# ProPrj_VacUBear_2026-03-05.net
KiCad netlist of a schematic drawn in EasyEDA Pro
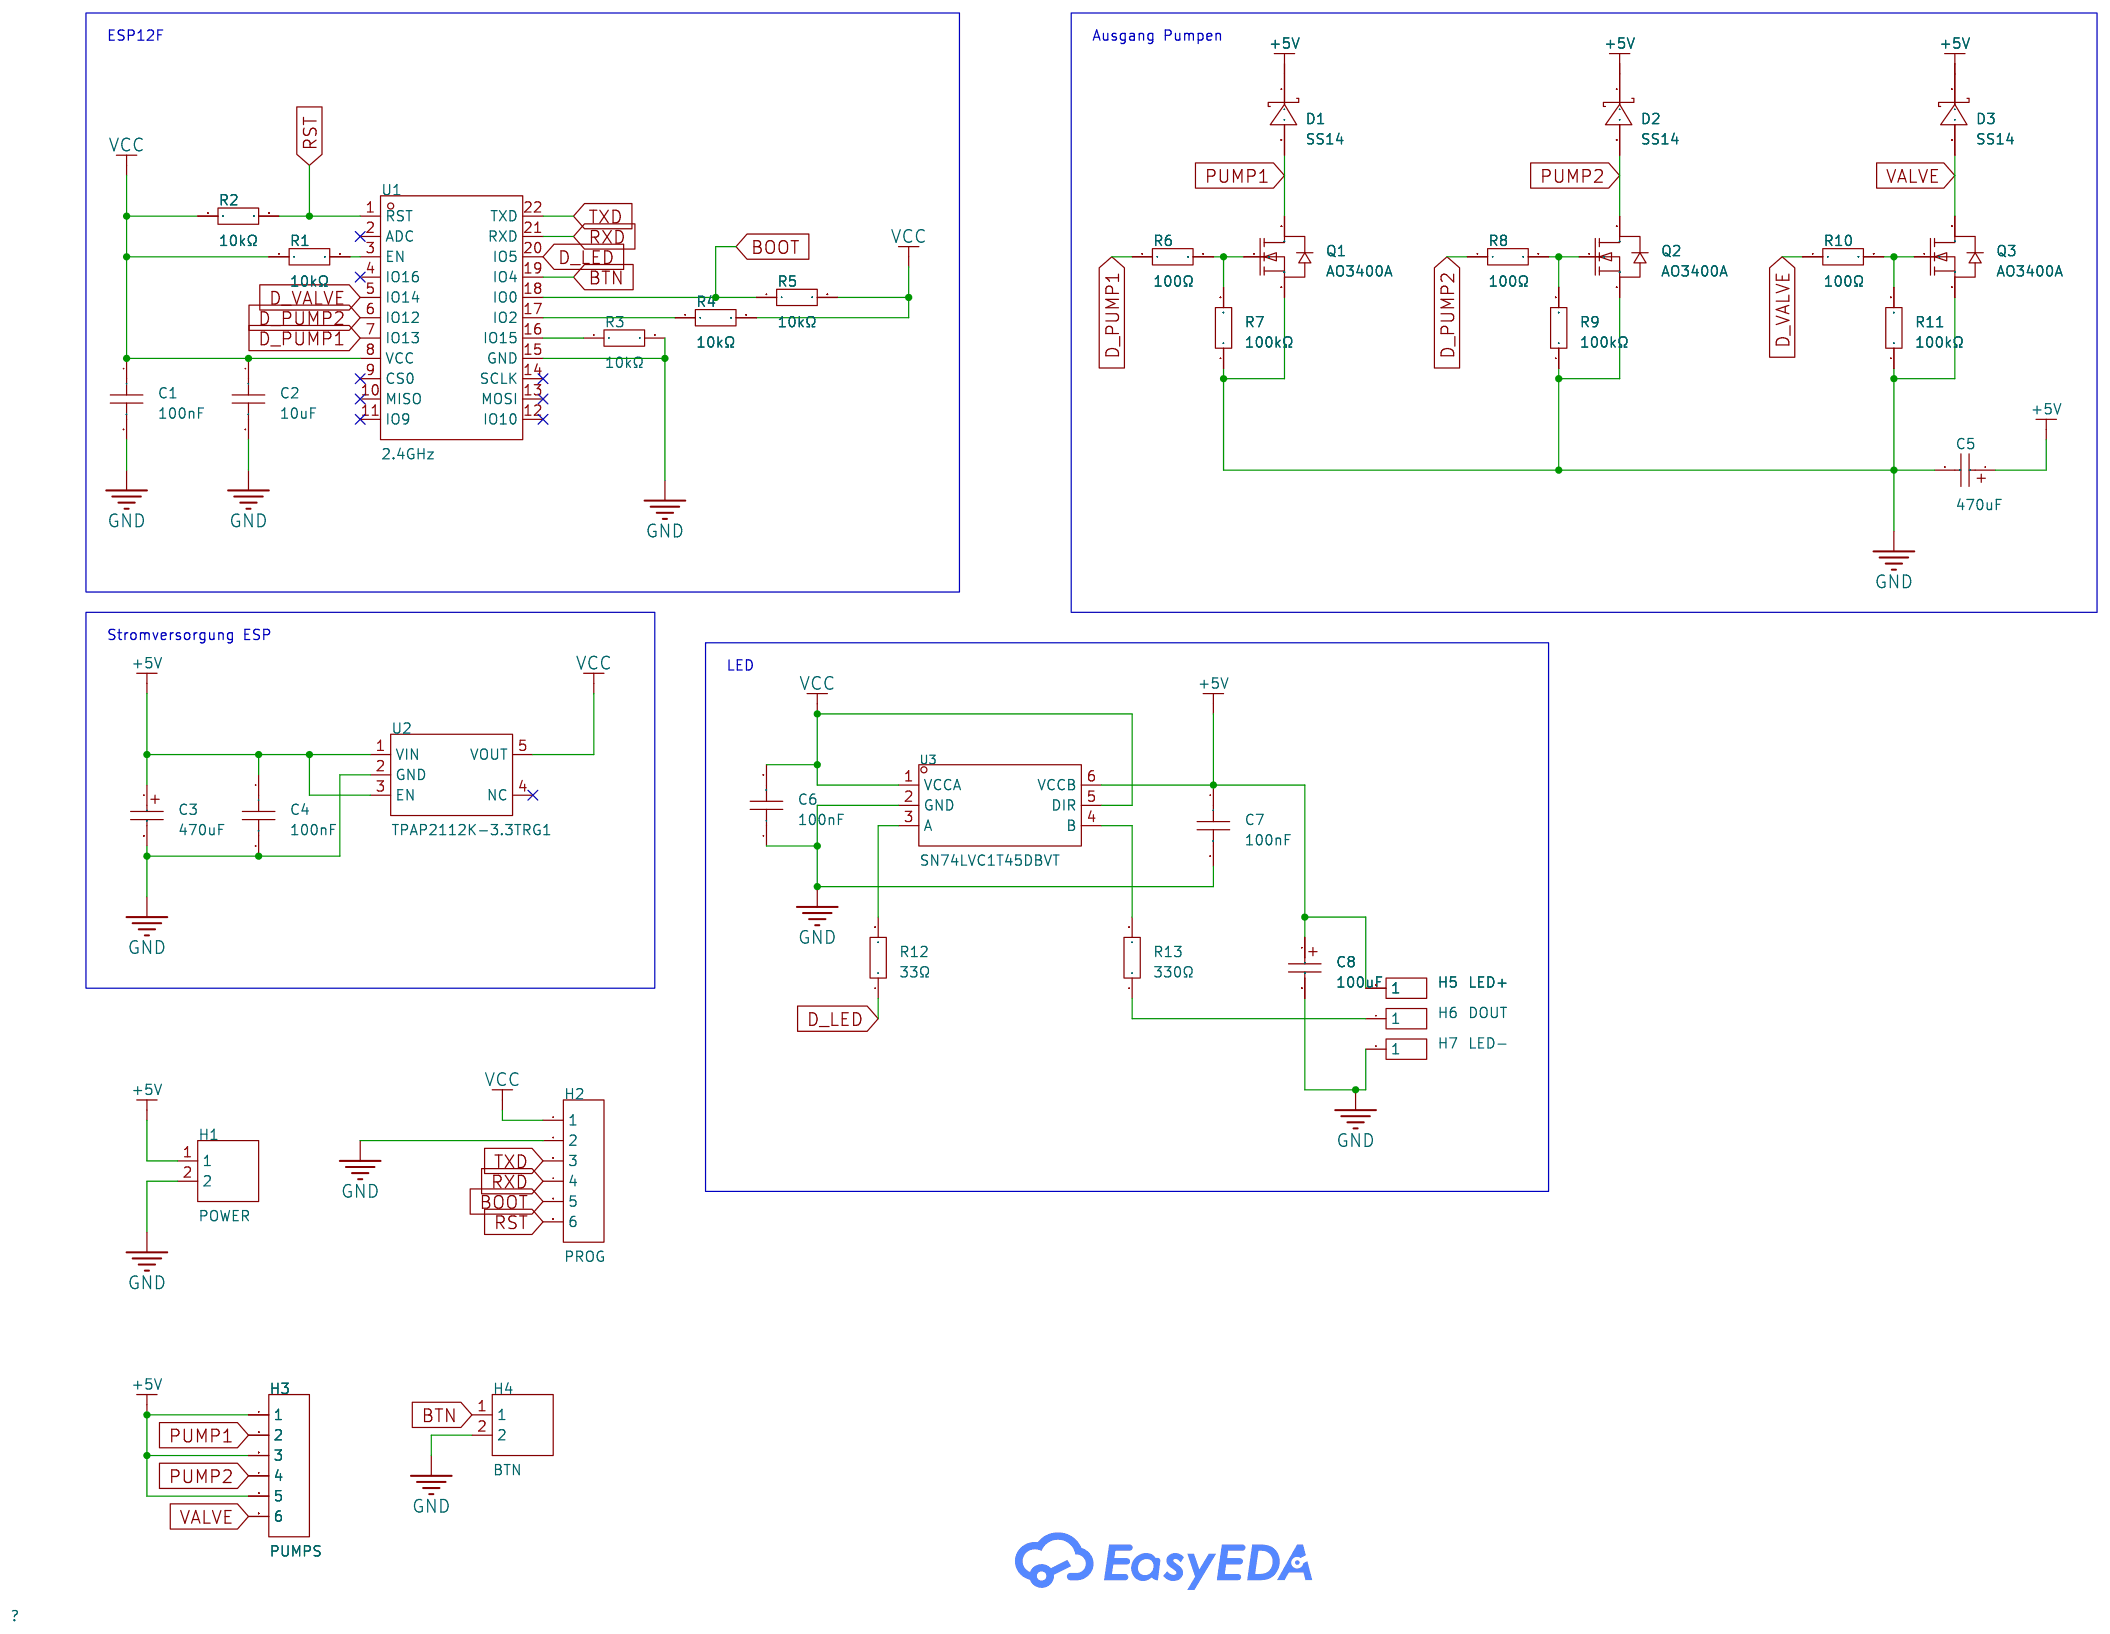
[diagram p0: schematic sheet]

(export (version "E")
  (design (tool "Eeschema 10.0.6"))
  (components
    (comp (ref "C1")
      (value "100nF")
      (footprint "easyedapro:C0402")
      (description "Capacitance:100nF Tolerance:±10% Tolerance:±10% Voltage Rating:50V Temperature Coefficient:X7R")
      (fields
        (field (name "Manufacturer Part") "CL05B104KB54PNC")
        (field (name "Manufacturer") "SAMSUNG(三星)")
      )
      (libsource (lib "easyedapro") (part "CAP"))
    )
    (comp (ref "C2")
      (value "10uF")
      (footprint "easyedapro:C0402")
      (description "Capacitance:10uF Tolerance:±20% Tolerance:±20% Voltage Rating:6.3V Temperature Coefficient:X5R")
      (fields
        (field (name "Manufacturer Part") "CL10A106MQ8NNNC")
        (field (name "Manufacturer") "SAMSUNG(三星)")
      )
      (libsource (lib "easyedapro") (part "CAP"))
    )
    (comp (ref "C3")
      (value "470uF")
      (footprint "easyedapro:CAP-SMD_BD3.0-L3.3-W3.3-RD")
      (fields (field (name "Manufacturer Part") "RVT1C471M0607") (field (name "Manufacturer") "ROQANG(容强)"))
      (libsource (lib "easyedapro") (part "C_Ele_SMD"))
    )
    (comp (ref "C4")
      (value "100nF")
      (footprint "easyedapro:C0402")
      (description "Capacitance:100nF Tolerance:±10% Tolerance:±10% Voltage Rating:50V Temperature Coefficient:X7R")
      (fields
        (field (name "Manufacturer Part") "CL05B104KB54PNC")
        (field (name "Manufacturer") "SAMSUNG(三星)")
      )
      (libsource (lib "easyedapro") (part "CAP"))
    )
    (comp (ref "C5")
      (value "470uF")
      (footprint "easyedapro:CAP-SMD_BD3.0-L3.3-W3.3-RD")
      (fields (field (name "Manufacturer Part") "RVT1C471M0607") (field (name "Manufacturer") "ROQANG(容强)"))
      (libsource (lib "easyedapro") (part "C_Ele_SMD"))
    )
    (comp (ref "C6")
      (value "100nF")
      (footprint "easyedapro:C0402")
      (description "Capacitance:100nF Tolerance:±10% Tolerance:±10% Voltage Rating:50V Temperature Coefficient:X7R")
      (fields
        (field (name "Manufacturer Part") "CL05B104KB54PNC")
        (field (name "Manufacturer") "SAMSUNG(三星)")
      )
      (libsource (lib "easyedapro") (part "CAP"))
    )
    (comp (ref "C7")
      (value "100nF")
      (footprint "easyedapro:C0402")
      (description "Capacitance:100nF Tolerance:±10% Tolerance:±10% Voltage Rating:50V Temperature Coefficient:X7R")
      (fields
        (field (name "Manufacturer Part") "CL05B104KB54PNC")
        (field (name "Manufacturer") "SAMSUNG(三星)")
      )
      (libsource (lib "easyedapro") (part "CAP"))
    )
    (comp (ref "C8")
      (value "100uF")
      (footprint "easyedapro:CAP-SMD_BD3.0-L3.3-W3.3-RD")
      (fields
        (field (name "Manufacturer Part") "RVT100UF16V67RV0016")
        (field (name "Manufacturer") "KNSCHA(科尼盛)")
      )
      (libsource (lib "easyedapro") (part "C_Ele_SMD"))
    )
    (comp (ref "D1")
      (value "SS14")
      (footprint "easyedapro:SMA_L4.2-W2.6-LS5.0-RD_1")
      (fields (field (name "Manufacturer") "MDD(辰达半导体)"))
      (libsource (lib "easyedapro") (part "SS14"))
    )
    (comp (ref "D2")
      (value "SS14")
      (footprint "easyedapro:SMA_L4.2-W2.6-LS5.0-RD_1")
      (fields (field (name "Manufacturer") "MDD(辰达半导体)"))
      (libsource (lib "easyedapro") (part "SS14"))
    )
    (comp (ref "D3")
      (value "SS14")
      (footprint "easyedapro:SMA_L4.2-W2.6-LS5.0-RD_1")
      (fields (field (name "Manufacturer") "MDD(辰达半导体)"))
      (libsource (lib "easyedapro") (part "SS14"))
    )
    (comp (ref "H1")
      (value "POWER")
      (footprint "easyedapro:HDR-TH_2P-P2.54-V-M-1")
      (libsource (lib "easyedapro") (part "210S-1*2P L=11.6MMGold-plated black"))
    )
    (comp (ref "H2")
      (value "PROG")
      (footprint "easyedapro:HDR-TH_6P-P2.54-V-M-1")
      (libsource (lib "easyedapro") (part "Header-Male-2.54_1x6"))
    )
    (comp (ref "H3")
      (value "PUMPS")
      (footprint "easyedapro:HDR-TH_6P-P2.54-V-M-1")
      (libsource (lib "easyedapro") (part "Header-Male-2.54_1x6"))
    )
    (comp (ref "H4")
      (value "BTN")
      (footprint "easyedapro:HDR-TH_2P-P2.54-V-M-1")
      (libsource (lib "easyedapro") (part "210S-1*2P L=11.6MMGold-plated black"))
    )
    (comp (ref "H5")
      (value "LED+")
      (footprint "easyedapro:HDR-TH_1P-V-M_XKB_X4611WV-01I-C28D40")
      (libsource (lib "easyedapro") (part "HDR_1x1"))
    )
    (comp (ref "H6")
      (value "DOUT")
      (footprint "easyedapro:HDR-TH_1P-V-M_XKB_X4611WV-01I-C28D40")
      (libsource (lib "easyedapro") (part "HDR_1x1"))
    )
    (comp (ref "H7")
      (value "LED-")
      (footprint "easyedapro:HDR-TH_1P-V-M_XKB_X4611WV-01I-C28D40")
      (libsource (lib "easyedapro") (part "HDR_1x1"))
    )
    (comp (ref "Q1")
      (value "AO3400A")
      (footprint "easyedapro:SOT-23-3_L2.9-W1.3-P1.90-LS2.4-BR")
      (fields (field (name "Manufacturer") "HUASHUO(华朔)"))
      (libsource (lib "easyedapro") (part "AO3400A_C700953"))
    )
    (comp (ref "Q2")
      (value "AO3400A")
      (footprint "easyedapro:SOT-23-3_L2.9-W1.3-P1.90-LS2.4-BR")
      (fields (field (name "Manufacturer") "HUASHUO(华朔)"))
      (libsource (lib "easyedapro") (part "AO3400A_C700953"))
    )
    (comp (ref "Q3")
      (value "AO3400A")
      (footprint "easyedapro:SOT-23-3_L2.9-W1.3-P1.90-LS2.4-BR")
      (fields (field (name "Manufacturer") "HUASHUO(华朔)"))
      (libsource (lib "easyedapro") (part "AO3400A_C700953"))
    )
    (comp (ref "R1")
      (value "10kΩ")
      (footprint "easyedapro:R0402")
      (fields (field (name "Manufacturer Part") "RC0402JR-0710KL") (field (name "Manufacturer") "YAGEO(国巨)"))
      (libsource (lib "easyedapro") (part "Res"))
    )
    (comp (ref "R2")
      (value "10kΩ")
      (footprint "easyedapro:R0402")
      (fields (field (name "Manufacturer Part") "RC0402JR-0710KL") (field (name "Manufacturer") "YAGEO(国巨)"))
      (libsource (lib "easyedapro") (part "Res"))
    )
    (comp (ref "R3")
      (value "10kΩ")
      (footprint "easyedapro:R0402")
      (fields (field (name "Manufacturer Part") "RC0402JR-0710KL") (field (name "Manufacturer") "YAGEO(国巨)"))
      (libsource (lib "easyedapro") (part "Res"))
    )
    (comp (ref "R4")
      (value "10kΩ")
      (footprint "easyedapro:R0402")
      (fields (field (name "Manufacturer Part") "RC0402JR-0710KL") (field (name "Manufacturer") "YAGEO(国巨)"))
      (libsource (lib "easyedapro") (part "Res"))
    )
    (comp (ref "R5")
      (value "10kΩ")
      (footprint "easyedapro:R0402")
      (fields (field (name "Manufacturer Part") "RC0402JR-0710KL") (field (name "Manufacturer") "YAGEO(国巨)"))
      (libsource (lib "easyedapro") (part "Res"))
    )
    (comp (ref "R6")
      (value "100Ω")
      (footprint "easyedapro:R0402")
      (fields (field (name "Manufacturer Part") "FRC0402F1000TS") (field (name "Manufacturer") "FOJAN(富捷)"))
      (libsource (lib "easyedapro") (part "Res"))
    )
    (comp (ref "R7")
      (value "100kΩ")
      (footprint "easyedapro:R0402")
      (fields (field (name "Manufacturer Part") "RC0402FR-07100KL") (field (name "Manufacturer") "YAGEO(国巨)"))
      (libsource (lib "easyedapro") (part "Res"))
    )
    (comp (ref "R8")
      (value "100Ω")
      (footprint "easyedapro:R0402")
      (fields (field (name "Manufacturer Part") "FRC0402F1000TS") (field (name "Manufacturer") "FOJAN(富捷)"))
      (libsource (lib "easyedapro") (part "Res"))
    )
    (comp (ref "R9")
      (value "100kΩ")
      (footprint "easyedapro:R0402")
      (fields (field (name "Manufacturer Part") "RC0402FR-07100KL") (field (name "Manufacturer") "YAGEO(国巨)"))
      (libsource (lib "easyedapro") (part "Res"))
    )
    (comp (ref "R10")
      (value "100Ω")
      (footprint "easyedapro:R0402")
      (fields (field (name "Manufacturer Part") "FRC0402F1000TS") (field (name "Manufacturer") "FOJAN(富捷)"))
      (libsource (lib "easyedapro") (part "Res"))
    )
    (comp (ref "R11")
      (value "100kΩ")
      (footprint "easyedapro:R0402")
      (fields (field (name "Manufacturer Part") "RC0402FR-07100KL") (field (name "Manufacturer") "YAGEO(国巨)"))
      (libsource (lib "easyedapro") (part "Res"))
    )
    (comp (ref "R12")
      (value "33Ω")
      (footprint "easyedapro:R0402")
      (fields (field (name "Manufacturer Part") "FRC0402F33R0TS") (field (name "Manufacturer") "FOJAN(富捷)"))
      (libsource (lib "easyedapro") (part "Res"))
    )
    (comp (ref "R13")
      (value "330Ω")
      (footprint "easyedapro:R0402")
      (fields (field (name "Manufacturer Part") "FRC0402F3300TS") (field (name "Manufacturer") "FOJAN(富捷)"))
      (libsource (lib "easyedapro") (part "Res"))
    )
    (comp (ref "U1")
      (value "2.4GHz")
      (footprint "easyedapro:WIRELM-SMD_ESP-12F")
      (fields (field (name "Manufacturer Part") "ESP-12F") (field (name "Manufacturer") "DOIT(四博智联)"))
      (libsource (lib "easyedapro") (part "ESP-12F"))
    )
    (comp (ref "U2")
      (value "TPAP2112K-3.3TRG1")
      (footprint "easyedapro:SOT-23-5_L2.9-W1.6-P0.95-LS2.8-BR")
      (fields (field (name "Manufacturer") "TECH PUBLIC(台舟)"))
      (libsource (lib "easyedapro") (part "TPAP2112K-3.3TRG1"))
    )
    (comp (ref "U3")
      (value "SN74LVC1T45DBVT")
      (footprint "easyedapro:SOT-23-6_L2.9-W1.6-P0.95-LS2.8-BR")
      (fields (field (name "Manufacturer") "TI(德州仪器)"))
      (libsource (lib "easyedapro") (part "SN74LVC1T45DBVT"))
    )
  )
  (nets
    (net (code "1") (name "+5V") (class "Default")
      (node (ref "C3") (pin "1") (pinfunction "1_1") (pintype "input"))
      (node (ref "C4") (pin "1") (pinfunction "1_1") (pintype "input"))
      (node (ref "C5") (pin "1") (pinfunction "1_1") (pintype "input"))
      (node (ref "C7") (pin "1") (pinfunction "1_1") (pintype "input"))
      (node (ref "C8") (pin "1") (pinfunction "1_1") (pintype "input"))
      (node (ref "D1") (pin "1") (pinfunction "K_1") (pintype "unspecified"))
      (node (ref "D2") (pin "1") (pinfunction "K_1") (pintype "unspecified"))
      (node (ref "D3") (pin "1") (pinfunction "K_1") (pintype "unspecified"))
      (node (ref "H1") (pin "1") (pinfunction "1_1") (pintype "unspecified"))
      (node (ref "H3") (pin "1") (pinfunction "1_1") (pintype "input"))
      (node (ref "H3") (pin "3") (pinfunction "3_3") (pintype "input"))
      (node (ref "H3") (pin "5") (pinfunction "5_5") (pintype "input"))
      (node (ref "H5") (pin "1") (pinfunction "1_1") (pintype "unspecified"))
      (node (ref "U2") (pin "1") (pinfunction "VIN_1") (pintype "unspecified"))
      (node (ref "U2") (pin "3") (pinfunction "EN_3") (pintype "unspecified"))
      (node (ref "U3") (pin "6") (pinfunction "VCCB_6") (pintype "input"))
    )
    (net (code "2") (name "BOOT") (class "Default")
      (node (ref "H2") (pin "5") (pinfunction "5_5") (pintype "input"))
      (node (ref "R5") (pin "1") (pinfunction "1_1") (pintype "input"))
      (node (ref "U1") (pin "18") (pinfunction "IO0_18") (pintype "unspecified"))
    )
    (net (code "3") (name "BTN") (class "Default")
      (node (ref "H4") (pin "1") (pinfunction "1_1") (pintype "unspecified"))
      (node (ref "U1") (pin "19") (pinfunction "IO4_19") (pintype "unspecified"))
    )
    (net (code "4") (name "D_LED") (class "Default")
      (node (ref "R12") (pin "1") (pinfunction "1_1") (pintype "input"))
      (node (ref "U1") (pin "20") (pinfunction "IO5_20") (pintype "unspecified"))
    )
    (net (code "5") (name "D_PUMP1") (class "Default")
      (node (ref "R6") (pin "1") (pinfunction "1_1") (pintype "input"))
      (node (ref "U1") (pin "7") (pinfunction "IO13_7") (pintype "unspecified"))
    )
    (net (code "6") (name "D_PUMP2") (class "Default")
      (node (ref "R8") (pin "1") (pinfunction "1_1") (pintype "input"))
      (node (ref "U1") (pin "6") (pinfunction "IO12_6") (pintype "unspecified"))
    )
    (net (code "7") (name "D_VALVE") (class "Default")
      (node (ref "R10") (pin "1") (pinfunction "1_1") (pintype "input"))
      (node (ref "U1") (pin "5") (pinfunction "IO14_5") (pintype "unspecified"))
    )
    (net (code "8") (name "GND") (class "Default")
      (node (ref "C1") (pin "2") (pinfunction "2_2") (pintype "input"))
      (node (ref "C2") (pin "2") (pinfunction "2_2") (pintype "input"))
      (node (ref "C3") (pin "2") (pinfunction "2_2") (pintype "input"))
      (node (ref "C4") (pin "2") (pinfunction "2_2") (pintype "input"))
      (node (ref "C5") (pin "2") (pinfunction "2_2") (pintype "input"))
      (node (ref "C6") (pin "1") (pinfunction "1_1") (pintype "input"))
      (node (ref "C7") (pin "2") (pinfunction "2_2") (pintype "input"))
      (node (ref "C8") (pin "2") (pinfunction "2_2") (pintype "input"))
      (node (ref "H1") (pin "2") (pinfunction "2_2") (pintype "unspecified"))
      (node (ref "H2") (pin "2") (pinfunction "2_2") (pintype "input"))
      (node (ref "H4") (pin "2") (pinfunction "2_2") (pintype "unspecified"))
      (node (ref "H7") (pin "1") (pinfunction "1_1") (pintype "unspecified"))
      (node (ref "Q1") (pin "2") (pinfunction "S_2") (pintype "unspecified"))
      (node (ref "Q2") (pin "2") (pinfunction "S_2") (pintype "unspecified"))
      (node (ref "Q3") (pin "2") (pinfunction "S_2") (pintype "unspecified"))
      (node (ref "R11") (pin "1") (pinfunction "1_1") (pintype "input"))
      (node (ref "R3") (pin "2") (pinfunction "2_2") (pintype "input"))
      (node (ref "R7") (pin "1") (pinfunction "1_1") (pintype "input"))
      (node (ref "R9") (pin "1") (pinfunction "1_1") (pintype "input"))
      (node (ref "U1") (pin "15") (pinfunction "GND_15") (pintype "unspecified"))
      (node (ref "U2") (pin "2") (pinfunction "GND_2") (pintype "unspecified"))
      (node (ref "U3") (pin "2") (pinfunction "GND_2") (pintype "input"))
    )
    (net (code "9") (name "Net-(H6-Pad1)") (class "Default")
      (node (ref "H6") (pin "1") (pinfunction "1_1") (pintype "unspecified"))
      (node (ref "R13") (pin "1") (pinfunction "1_1") (pintype "input"))
    )
    (net (code "10") (name "Net-(Q1-G)") (class "Default")
      (node (ref "Q1") (pin "1") (pinfunction "G_1") (pintype "unspecified"))
      (node (ref "R6") (pin "2") (pinfunction "2_2") (pintype "input"))
      (node (ref "R7") (pin "2") (pinfunction "2_2") (pintype "input"))
    )
    (net (code "11") (name "Net-(Q2-G)") (class "Default")
      (node (ref "Q2") (pin "1") (pinfunction "G_1") (pintype "unspecified"))
      (node (ref "R8") (pin "2") (pinfunction "2_2") (pintype "input"))
      (node (ref "R9") (pin "2") (pinfunction "2_2") (pintype "input"))
    )
    (net (code "12") (name "Net-(Q3-G)") (class "Default")
      (node (ref "Q3") (pin "1") (pinfunction "G_1") (pintype "unspecified"))
      (node (ref "R10") (pin "2") (pinfunction "2_2") (pintype "input"))
      (node (ref "R11") (pin "2") (pinfunction "2_2") (pintype "input"))
    )
    (net (code "13") (name "Net-(U1-EN)") (class "Default")
      (node (ref "R1") (pin "2") (pinfunction "2_2") (pintype "input"))
      (node (ref "U1") (pin "3") (pinfunction "EN_3") (pintype "unspecified"))
    )
    (net (code "14") (name "Net-(U1-IO2)") (class "Default")
      (node (ref "R4") (pin "1") (pinfunction "1_1") (pintype "input"))
      (node (ref "U1") (pin "17") (pinfunction "IO2_17") (pintype "unspecified"))
    )
    (net (code "15") (name "Net-(U1-IO15)") (class "Default")
      (node (ref "R3") (pin "1") (pinfunction "1_1") (pintype "input"))
      (node (ref "U1") (pin "16") (pinfunction "IO15_16") (pintype "unspecified"))
    )
    (net (code "16") (name "Net-(U3-A)") (class "Default")
      (node (ref "R12") (pin "2") (pinfunction "2_2") (pintype "input"))
      (node (ref "U3") (pin "3") (pinfunction "A_3") (pintype "input"))
    )
    (net (code "17") (name "Net-(U3-B)") (class "Default")
      (node (ref "R13") (pin "2") (pinfunction "2_2") (pintype "input"))
      (node (ref "U3") (pin "4") (pinfunction "B_4") (pintype "input"))
    )
    (net (code "18") (name "PUMP1") (class "Default")
      (node (ref "D1") (pin "2") (pinfunction "A_2") (pintype "unspecified"))
      (node (ref "H3") (pin "2") (pinfunction "2_2") (pintype "input"))
      (node (ref "Q1") (pin "3") (pinfunction "D_3") (pintype "unspecified"))
    )
    (net (code "19") (name "PUMP2") (class "Default")
      (node (ref "D2") (pin "2") (pinfunction "A_2") (pintype "unspecified"))
      (node (ref "H3") (pin "4") (pinfunction "4_4") (pintype "input"))
      (node (ref "Q2") (pin "3") (pinfunction "D_3") (pintype "unspecified"))
    )
    (net (code "20") (name "RST") (class "Default")
      (node (ref "H2") (pin "6") (pinfunction "6_6") (pintype "input"))
      (node (ref "R2") (pin "2") (pinfunction "2_2") (pintype "input"))
      (node (ref "U1") (pin "1") (pinfunction "RST_1") (pintype "unspecified"))
    )
    (net (code "21") (name "RXD") (class "Default")
      (node (ref "H2") (pin "4") (pinfunction "4_4") (pintype "input"))
      (node (ref "U1") (pin "21") (pinfunction "RXD_21") (pintype "unspecified"))
    )
    (net (code "22") (name "TXD") (class "Default")
      (node (ref "H2") (pin "3") (pinfunction "3_3") (pintype "input"))
      (node (ref "U1") (pin "22") (pinfunction "TXD_22") (pintype "unspecified"))
    )
    (net (code "23") (name "VALVE") (class "Default")
      (node (ref "D3") (pin "2") (pinfunction "A_2") (pintype "unspecified"))
      (node (ref "H3") (pin "6") (pinfunction "6_6") (pintype "input"))
      (node (ref "Q3") (pin "3") (pinfunction "D_3") (pintype "unspecified"))
    )
    (net (code "24") (name "VCC") (class "Default")
      (node (ref "C1") (pin "1") (pinfunction "1_1") (pintype "input"))
      (node (ref "C2") (pin "1") (pinfunction "1_1") (pintype "input"))
      (node (ref "C6") (pin "2") (pinfunction "2_2") (pintype "input"))
      (node (ref "H2") (pin "1") (pinfunction "1_1") (pintype "input"))
      (node (ref "R1") (pin "1") (pinfunction "1_1") (pintype "input"))
      (node (ref "R2") (pin "1") (pinfunction "1_1") (pintype "input"))
      (node (ref "R4") (pin "2") (pinfunction "2_2") (pintype "input"))
      (node (ref "R5") (pin "2") (pinfunction "2_2") (pintype "input"))
      (node (ref "U1") (pin "8") (pinfunction "VCC_8") (pintype "unspecified"))
      (node (ref "U2") (pin "5") (pinfunction "VOUT_5") (pintype "unspecified"))
      (node (ref "U3") (pin "1") (pinfunction "VCCA_1") (pintype "input"))
      (node (ref "U3") (pin "5") (pinfunction "DIR_5") (pintype "input"))
    )
    (net (code "25") (name "unconnected-(U1-ADC-Pad2)") (class "Default")
      (node (ref "U1") (pin "2") (pinfunction "ADC_2") (pintype "unspecified+no_connect"))
    )
    (net (code "26") (name "unconnected-(U1-CS0-Pad9)") (class "Default")
      (node (ref "U1") (pin "9") (pinfunction "CS0_9") (pintype "unspecified+no_connect"))
    )
    (net (code "27") (name "unconnected-(U1-IO9-Pad11)") (class "Default")
      (node (ref "U1") (pin "11") (pinfunction "IO9_11") (pintype "unspecified+no_connect"))
    )
    (net (code "28") (name "unconnected-(U1-IO10-Pad12)") (class "Default")
      (node (ref "U1") (pin "12") (pinfunction "IO10_12") (pintype "unspecified+no_connect"))
    )
    (net (code "29") (name "unconnected-(U1-IO16-Pad4)") (class "Default")
      (node (ref "U1") (pin "4") (pinfunction "IO16_4") (pintype "unspecified+no_connect"))
    )
    (net (code "30") (name "unconnected-(U1-MISO-Pad10)") (class "Default")
      (node (ref "U1") (pin "10") (pinfunction "MISO_10") (pintype "unspecified+no_connect"))
    )
    (net (code "31") (name "unconnected-(U1-MOSI-Pad13)") (class "Default")
      (node (ref "U1") (pin "13") (pinfunction "MOSI_13") (pintype "unspecified+no_connect"))
    )
    (net (code "32") (name "unconnected-(U1-SCLK-Pad14)") (class "Default")
      (node (ref "U1") (pin "14") (pinfunction "SCLK_14") (pintype "unspecified+no_connect"))
    )
    (net (code "33") (name "unconnected-(U2-NC-Pad4)") (class "Default")
      (node (ref "U2") (pin "4") (pinfunction "NC_4") (pintype "unspecified+no_connect"))
    )
  )
)
